# FM24W256Shield.net
KiCad netlist of a schematic drawn in EAGLE
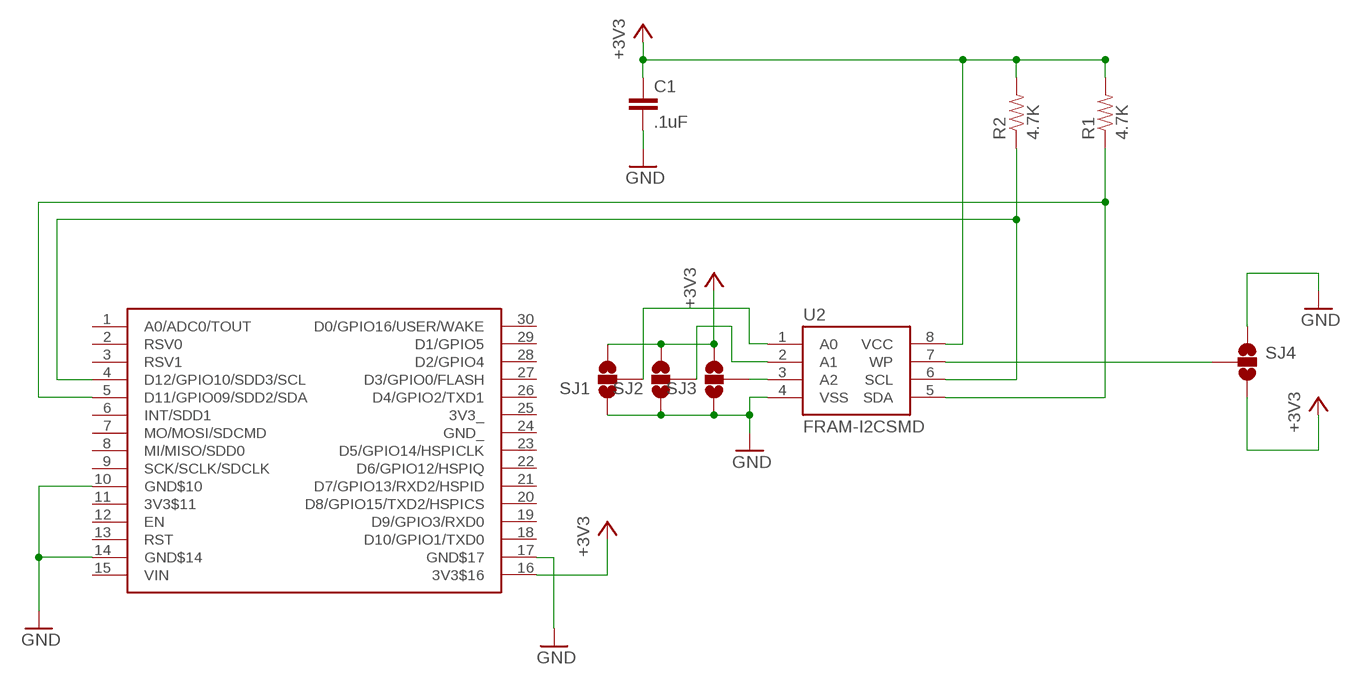
[diagram p0: schematic, sheet 1]

(export (version "E")
  (design (tool "Eeschema 10.0.6"))
  (components
    (comp (ref "C1")
      (value ".1uF")
      (footprint "eagle-import:0603-CAP")
      (libsource (lib "eagle-import") (part "CAP0603-CAP"))
    )
    (comp (ref "R1")
      (value "4.7K")
      (footprint "eagle-import:0603-RES")
      (libsource (lib "eagle-import") (part "RESISTOR0603-RES"))
    )
    (comp (ref "R2")
      (value "4.7K")
      (footprint "eagle-import:0603-RES")
      (libsource (lib "eagle-import") (part "RESISTOR0603-RES"))
    )
    (comp (ref "SJ1")
      (value "SOLDERJUMPER_2WAYPASTE1&2")
      (footprint "eagle-import:SJ_3_PASTE1&2")
      (libsource (lib "eagle-import") (part "SOLDERJUMPER_2WAYPASTE1&2"))
    )
    (comp (ref "SJ2")
      (value "SOLDERJUMPER_2WAYPASTE1&2")
      (footprint "eagle-import:SJ_3_PASTE1&2")
      (libsource (lib "eagle-import") (part "SOLDERJUMPER_2WAYPASTE1&2"))
    )
    (comp (ref "SJ3")
      (value "SOLDERJUMPER_2WAYPASTE1&2")
      (footprint "eagle-import:SJ_3_PASTE1&2")
      (libsource (lib "eagle-import") (part "SOLDERJUMPER_2WAYPASTE1&2"))
    )
    (comp (ref "SJ4")
      (value "SOLDERJUMPER_2WAYPASTE1&2")
      (footprint "eagle-import:SJ_3_PASTE1&2")
      (libsource (lib "eagle-import") (part "SOLDERJUMPER_2WAYPASTE1&2"))
    )
    (comp (ref "U$2")
      (value "NERDSHIELD")
      (footprint "eagle-import:NERDUINO_STACK")
      (libsource (lib "eagle-import") (part "NERDSHIELD"))
    )
    (comp (ref "U2")
      (value "FRAM-I2CSMD")
      (footprint "eagle-import:SO08")
      (libsource (lib "eagle-import") (part "FRAM-I2CSMD"))
    )
  )
  (nets
    (net (code "1") (name "+3V3") (class "Default")
      (node (ref "C1") (pin "1") (pinfunction "1_1") (pintype "passive"))
      (node (ref "R1") (pin "2") (pinfunction "2_2") (pintype "passive"))
      (node (ref "R2") (pin "2") (pinfunction "2_2") (pintype "passive"))
      (node (ref "SJ1") (pin "3") (pinfunction "3_3") (pintype "passive"))
      (node (ref "SJ2") (pin "3") (pinfunction "3_3") (pintype "passive"))
      (node (ref "SJ3") (pin "3") (pinfunction "3_3") (pintype "passive"))
      (node (ref "SJ4") (pin "3") (pinfunction "3_3") (pintype "passive"))
      (node (ref "U$2") (pin "16") (pinfunction "3V3$16_16") (pintype "bidirectional"))
      (node (ref "U2") (pin "8") (pinfunction "VCC_8") (pintype "power_in"))
    )
    (net (code "2") (name "GND") (class "Default")
      (node (ref "C1") (pin "2") (pinfunction "2_2") (pintype "passive"))
      (node (ref "SJ1") (pin "1") (pinfunction "1_1") (pintype "passive"))
      (node (ref "SJ2") (pin "1") (pinfunction "1_1") (pintype "passive"))
      (node (ref "SJ3") (pin "1") (pinfunction "1_1") (pintype "passive"))
      (node (ref "SJ4") (pin "1") (pinfunction "1_1") (pintype "passive"))
      (node (ref "U$2") (pin "10") (pinfunction "GND$10_10") (pintype "bidirectional"))
      (node (ref "U$2") (pin "14") (pinfunction "GND$14_14") (pintype "bidirectional"))
      (node (ref "U$2") (pin "17") (pinfunction "GND$17_17") (pintype "bidirectional"))
      (node (ref "U2") (pin "4") (pinfunction "VSS_4") (pintype "power_in"))
    )
    (net (code "3") (name "Net-(U$2-D11{slash}GPIO09{slash}SDD2{slash}SDA)") (class "Default")
      (node (ref "R1") (pin "1") (pinfunction "1_1") (pintype "passive"))
      (node (ref "U$2") (pin "5") (pinfunction "D11/GPIO09/SDD2/SDA_5") (pintype "bidirectional"))
      (node (ref "U2") (pin "5") (pinfunction "SDA_5") (pintype "bidirectional"))
    )
    (net (code "4") (name "Net-(U$2-D12{slash}GPIO10{slash}SDD3{slash}SCL)") (class "Default")
      (node (ref "R2") (pin "1") (pinfunction "1_1") (pintype "passive"))
      (node (ref "U$2") (pin "4") (pinfunction "D12/GPIO10/SDD3/SCL_4") (pintype "bidirectional"))
      (node (ref "U2") (pin "6") (pinfunction "SCL_6") (pintype "bidirectional"))
    )
    (net (code "5") (name "Net-(U2-A0)") (class "Default")
      (node (ref "SJ1") (pin "2") (pinfunction "2_2") (pintype "passive"))
      (node (ref "U2") (pin "1") (pinfunction "A0_1") (pintype "bidirectional"))
    )
    (net (code "6") (name "Net-(U2-A1)") (class "Default")
      (node (ref "SJ2") (pin "2") (pinfunction "2_2") (pintype "passive"))
      (node (ref "U2") (pin "2") (pinfunction "A1_2") (pintype "bidirectional"))
    )
    (net (code "7") (name "Net-(U2-A2)") (class "Default")
      (node (ref "SJ3") (pin "2") (pinfunction "2_2") (pintype "passive"))
      (node (ref "U2") (pin "3") (pinfunction "A2_3") (pintype "bidirectional"))
    )
    (net (code "8") (name "Net-(U2-WP)") (class "Default")
      (node (ref "SJ4") (pin "2") (pinfunction "2_2") (pintype "passive"))
      (node (ref "U2") (pin "7") (pinfunction "WP_7") (pintype "bidirectional"))
    )
    (net (code "9") (name "unconnected-(U$2-3V3$11-Pad11)") (class "Default")
      (node (ref "U$2") (pin "11") (pinfunction "3V3$11_11") (pintype "bidirectional"))
    )
    (net (code "10") (name "unconnected-(U$2-3V3_-Pad25)") (class "Default")
      (node (ref "U$2") (pin "25") (pinfunction "3V3__25") (pintype "bidirectional"))
    )
    (net (code "11") (name "unconnected-(U$2-A0{slash}ADC0{slash}TOUT-Pad1)") (class "Default")
      (node (ref "U$2") (pin "1") (pinfunction "A0/ADC0/TOUT_1") (pintype "bidirectional"))
    )
    (net (code "12") (name "unconnected-(U$2-D0{slash}GPIO16{slash}USER{slash}WAKE-Pad30)") (class "Default")
      (node (ref "U$2") (pin "30") (pinfunction "D0/GPIO16/USER/WAKE_30") (pintype "bidirectional"))
    )
    (net (code "13") (name "unconnected-(U$2-D1{slash}GPIO5-Pad29)") (class "Default")
      (node (ref "U$2") (pin "29") (pinfunction "D1/GPIO5_29") (pintype "bidirectional"))
    )
    (net (code "14") (name "unconnected-(U$2-D2{slash}GPIO4-Pad28)") (class "Default")
      (node (ref "U$2") (pin "28") (pinfunction "D2/GPIO4_28") (pintype "bidirectional"))
    )
    (net (code "15") (name "unconnected-(U$2-D3{slash}GPIO0{slash}FLASH-Pad27)") (class "Default")
      (node (ref "U$2") (pin "27") (pinfunction "D3/GPIO0/FLASH_27") (pintype "bidirectional"))
    )
    (net (code "16") (name "unconnected-(U$2-D4{slash}GPIO2{slash}TXD1-Pad26)") (class "Default")
      (node (ref "U$2") (pin "26") (pinfunction "D4/GPIO2/TXD1_26") (pintype "bidirectional"))
    )
    (net (code "17") (name "unconnected-(U$2-D5{slash}GPIO14{slash}HSPICLK-Pad23)") (class "Default")
      (node (ref "U$2") (pin "23") (pinfunction "D5/GPIO14/HSPICLK_23") (pintype "bidirectional"))
    )
    (net (code "18") (name "unconnected-(U$2-D6{slash}GPIO12{slash}HSPIQ-Pad22)") (class "Default")
      (node (ref "U$2") (pin "22") (pinfunction "D6/GPIO12/HSPIQ_22") (pintype "bidirectional"))
    )
    (net (code "19") (name "unconnected-(U$2-D7{slash}GPIO13{slash}RXD2{slash}HSPID-Pad21)") (class "Default")
      (node (ref "U$2") (pin "21") (pinfunction "D7/GPIO13/RXD2/HSPID_21") (pintype "bidirectional"))
    )
    (net (code "20") (name "unconnected-(U$2-D8{slash}GPIO15{slash}TXD2{slash}HSPICS-Pad20)") (class "Default")
      (node (ref "U$2") (pin "20") (pinfunction "D8/GPIO15/TXD2/HSPICS_20") (pintype "bidirectional"))
    )
    (net (code "21") (name "unconnected-(U$2-D9{slash}GPIO3{slash}RXD0-Pad19)") (class "Default")
      (node (ref "U$2") (pin "19") (pinfunction "D9/GPIO3/RXD0_19") (pintype "bidirectional"))
    )
    (net (code "22") (name "unconnected-(U$2-D10{slash}GPIO1{slash}TXD0-Pad18)") (class "Default")
      (node (ref "U$2") (pin "18") (pinfunction "D10/GPIO1/TXD0_18") (pintype "bidirectional"))
    )
    (net (code "23") (name "unconnected-(U$2-EN-Pad12)") (class "Default")
      (node (ref "U$2") (pin "12") (pinfunction "EN_12") (pintype "bidirectional"))
    )
    (net (code "24") (name "unconnected-(U$2-GND_-Pad24)") (class "Default")
      (node (ref "U$2") (pin "24") (pinfunction "GND__24") (pintype "bidirectional"))
    )
    (net (code "25") (name "unconnected-(U$2-INT{slash}SDD1-Pad6)") (class "Default")
      (node (ref "U$2") (pin "6") (pinfunction "INT/SDD1_6") (pintype "bidirectional"))
    )
    (net (code "26") (name "unconnected-(U$2-MI{slash}MISO{slash}SDD0-Pad8)") (class "Default")
      (node (ref "U$2") (pin "8") (pinfunction "MI/MISO/SDD0_8") (pintype "bidirectional"))
    )
    (net (code "27") (name "unconnected-(U$2-MO{slash}MOSI{slash}SDCMD-Pad7)") (class "Default")
      (node (ref "U$2") (pin "7") (pinfunction "MO/MOSI/SDCMD_7") (pintype "bidirectional"))
    )
    (net (code "28") (name "unconnected-(U$2-RST-Pad13)") (class "Default")
      (node (ref "U$2") (pin "13") (pinfunction "RST_13") (pintype "bidirectional"))
    )
    (net (code "29") (name "unconnected-(U$2-RSV0-Pad2)") (class "Default")
      (node (ref "U$2") (pin "2") (pinfunction "RSV0_2") (pintype "bidirectional"))
    )
    (net (code "30") (name "unconnected-(U$2-RSV1-Pad3)") (class "Default")
      (node (ref "U$2") (pin "3") (pinfunction "RSV1_3") (pintype "bidirectional"))
    )
    (net (code "31") (name "unconnected-(U$2-SCK{slash}SCLK{slash}SDCLK-Pad9)") (class "Default")
      (node (ref "U$2") (pin "9") (pinfunction "SCK/SCLK/SDCLK_9") (pintype "bidirectional"))
    )
    (net (code "32") (name "unconnected-(U$2-VIN-Pad15)") (class "Default")
      (node (ref "U$2") (pin "15") (pinfunction "VIN_15") (pintype "bidirectional"))
    )
  )
)
